# ThermoTop_C.net
KiCad netlist of a schematic drawn in EAGLE
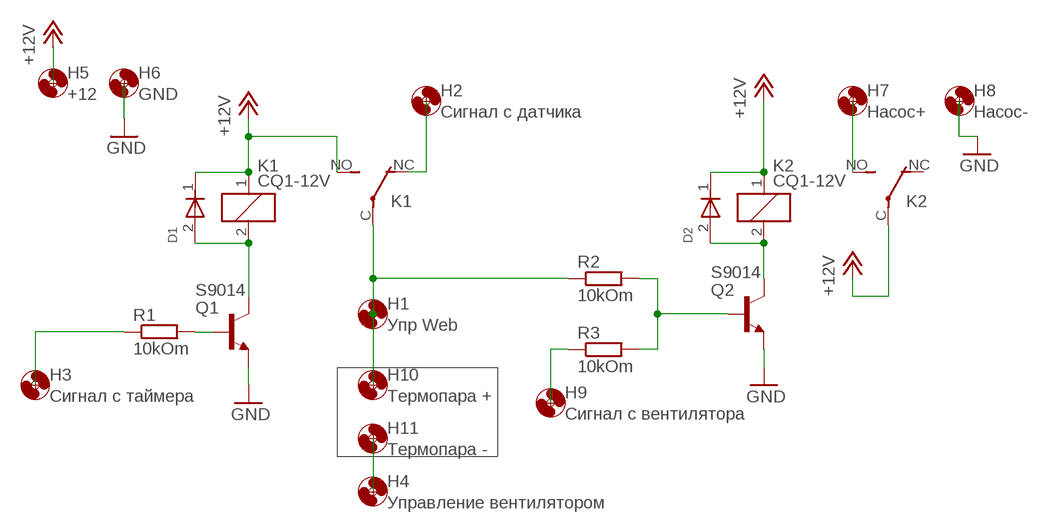
[diagram p0: schematic, sheet 1]

(export (version "E")
  (design (tool "Eeschema 10.0.6"))
  (components
    (comp (ref "D1")
      (value "DIODE")
      (footprint "eagle-import:SOD80")
      (libsource (lib "eagle-import") (part "DIODE"))
    )
    (comp (ref "D2")
      (value "DIODE")
      (footprint "eagle-import:SOD80")
      (libsource (lib "eagle-import") (part "DIODE"))
    )
    (comp (ref "H1")
      (value "Упр Web")
      (footprint "eagle-import:2,8")
      (libsource (lib "eagle-import") (part "MOUNT-HOLE2.8"))
    )
    (comp (ref "H2")
      (value "Сигнал с датчика")
      (footprint "eagle-import:2,8")
      (libsource (lib "eagle-import") (part "MOUNT-HOLE2.8"))
    )
    (comp (ref "H3")
      (value "Сигнал с таймера")
      (footprint "eagle-import:2,8")
      (libsource (lib "eagle-import") (part "MOUNT-HOLE2.8"))
    )
    (comp (ref "H4")
      (value "Управление вентилятором")
      (footprint "eagle-import:2,8")
      (libsource (lib "eagle-import") (part "MOUNT-HOLE2.8"))
    )
    (comp (ref "H5")
      (value "+12")
      (footprint "eagle-import:3,0")
      (libsource (lib "eagle-import") (part "MOUNT-HOLE3.0"))
    )
    (comp (ref "H6")
      (value "GND")
      (footprint "eagle-import:3,0")
      (libsource (lib "eagle-import") (part "MOUNT-HOLE3.0"))
    )
    (comp (ref "H7")
      (value "Насос+")
      (footprint "eagle-import:3,0")
      (libsource (lib "eagle-import") (part "MOUNT-HOLE3.0"))
    )
    (comp (ref "H8")
      (value "Насос-")
      (footprint "eagle-import:3,0")
      (libsource (lib "eagle-import") (part "MOUNT-HOLE3.0"))
    )
    (comp (ref "H9")
      (value "Сигнал с вентилятора")
      (footprint "eagle-import:2,8")
      (libsource (lib "eagle-import") (part "MOUNT-HOLE2.8"))
    )
    (comp (ref "H10")
      (value "Термопара +")
      (footprint "eagle-import:2,8")
      (libsource (lib "eagle-import") (part "MOUNT-HOLE2.8"))
    )
    (comp (ref "H11")
      (value "Термопара -")
      (footprint "eagle-import:2,8")
      (libsource (lib "eagle-import") (part "MOUNT-HOLE2.8"))
    )
    (comp (ref "K1")
      (value "CQ1-12V")
      (footprint "eagle-import:CQ1")
      (libsource (lib "eagle-import") (part "CQ1-12V"))
    )
    (comp (ref "K2")
      (value "CQ1-12V")
      (footprint "eagle-import:CQ1")
      (libsource (lib "eagle-import") (part "CQ1-12V"))
    )
    (comp (ref "Q1")
      (value "S9014")
      (footprint "eagle-import:TO92")
      (libsource (lib "eagle-import") (part "2N3904"))
    )
    (comp (ref "Q2")
      (value "S9014")
      (footprint "eagle-import:TO92")
      (libsource (lib "eagle-import") (part "2N3904"))
    )
    (comp (ref "R1")
      (value "10kOm")
      (footprint "eagle-import:R0603")
      (libsource (lib "eagle-import") (part "R-EU_R0603"))
    )
    (comp (ref "R2")
      (value "10kOm")
      (footprint "eagle-import:R0603")
      (libsource (lib "eagle-import") (part "R-EU_R0603"))
    )
    (comp (ref "R3")
      (value "10kOm")
      (footprint "eagle-import:R0603")
      (libsource (lib "eagle-import") (part "R-EU_R0603"))
    )
  )
  (nets
    (net (code "1") (name "+12V") (class "Default")
      (node (ref "D1") (pin "1") (pinfunction "KATOD_1") (pintype "power_in"))
      (node (ref "D2") (pin "1") (pinfunction "KATOD_1") (pintype "power_in"))
      (node (ref "H5") (pin "P$1") (pinfunction "P$1_P$1") (pintype "bidirectional"))
      (node (ref "K1") (pin "1") (pinfunction "1_1") (pintype "passive"))
      (node (ref "K1") (pin "NO") (pinfunction "S_NO") (pintype "passive"))
      (node (ref "K2") (pin "1") (pinfunction "1_1") (pintype "passive"))
      (node (ref "K2") (pin "C") (pinfunction "P_C") (pintype "passive"))
    )
    (net (code "2") (name "GND") (class "Default")
      (node (ref "H6") (pin "P$1") (pinfunction "P$1_P$1") (pintype "bidirectional"))
      (node (ref "H8") (pin "P$1") (pinfunction "P$1_P$1") (pintype "bidirectional"))
      (node (ref "Q1") (pin "3") (pinfunction "E_3") (pintype "passive"))
      (node (ref "Q2") (pin "3") (pinfunction "E_3") (pintype "passive"))
    )
    (net (code "3") (name "Net-(D1-ANOD)") (class "Default")
      (node (ref "D1") (pin "2") (pinfunction "ANOD_2") (pintype "power_in"))
      (node (ref "K1") (pin "2") (pinfunction "2_2") (pintype "passive"))
      (node (ref "Q1") (pin "1") (pinfunction "C_1") (pintype "passive"))
    )
    (net (code "4") (name "Net-(D2-ANOD)") (class "Default")
      (node (ref "D2") (pin "2") (pinfunction "ANOD_2") (pintype "power_in"))
      (node (ref "K2") (pin "2") (pinfunction "2_2") (pintype "passive"))
      (node (ref "Q2") (pin "1") (pinfunction "C_1") (pintype "passive"))
    )
    (net (code "5") (name "Net-(H3-PadP$1)") (class "Default")
      (node (ref "H3") (pin "P$1") (pinfunction "P$1_P$1") (pintype "bidirectional"))
      (node (ref "R1") (pin "1") (pinfunction "1_1") (pintype "passive"))
    )
    (net (code "6") (name "Net-(H9-PadP$1)") (class "Default")
      (node (ref "H9") (pin "P$1") (pinfunction "P$1_P$1") (pintype "bidirectional"))
      (node (ref "R3") (pin "1") (pinfunction "1_1") (pintype "passive"))
    )
    (net (code "7") (name "Net-(H11-PadP$1)") (class "Default")
      (node (ref "H11") (pin "P$1") (pinfunction "P$1_P$1") (pintype "bidirectional"))
      (node (ref "H4") (pin "P$1") (pinfunction "P$1_P$1") (pintype "bidirectional"))
    )
    (net (code "8") (name "Net-(K1B-O)") (class "Default")
      (node (ref "H2") (pin "P$1") (pinfunction "P$1_P$1") (pintype "bidirectional"))
      (node (ref "K1") (pin "NC") (pinfunction "O_NC") (pintype "passive"))
    )
    (net (code "9") (name "Net-(K1B-P)") (class "Default")
      (node (ref "H1") (pin "P$1") (pinfunction "P$1_P$1") (pintype "bidirectional"))
      (node (ref "H10") (pin "P$1") (pinfunction "P$1_P$1") (pintype "bidirectional"))
      (node (ref "K1") (pin "C") (pinfunction "P_C") (pintype "passive"))
      (node (ref "R2") (pin "1") (pinfunction "1_1") (pintype "passive"))
    )
    (net (code "10") (name "Net-(K2B-S)") (class "Default")
      (node (ref "H7") (pin "P$1") (pinfunction "P$1_P$1") (pintype "bidirectional"))
      (node (ref "K2") (pin "NO") (pinfunction "S_NO") (pintype "passive"))
    )
    (net (code "11") (name "Net-(Q1-B)") (class "Default")
      (node (ref "Q1") (pin "2") (pinfunction "B_2") (pintype "passive"))
      (node (ref "R1") (pin "2") (pinfunction "2_2") (pintype "passive"))
    )
    (net (code "12") (name "Net-(Q2-B)") (class "Default")
      (node (ref "Q2") (pin "2") (pinfunction "B_2") (pintype "passive"))
      (node (ref "R2") (pin "2") (pinfunction "2_2") (pintype "passive"))
      (node (ref "R3") (pin "2") (pinfunction "2_2") (pintype "passive"))
    )
    (net (code "13") (name "unconnected-(K2B-O-PadNC)") (class "Default")
      (node (ref "K2") (pin "NC") (pinfunction "O_NC") (pintype "passive"))
    )
  )
)
